# boost.net
KiCad netlist of a schematic drawn in Altium Designer
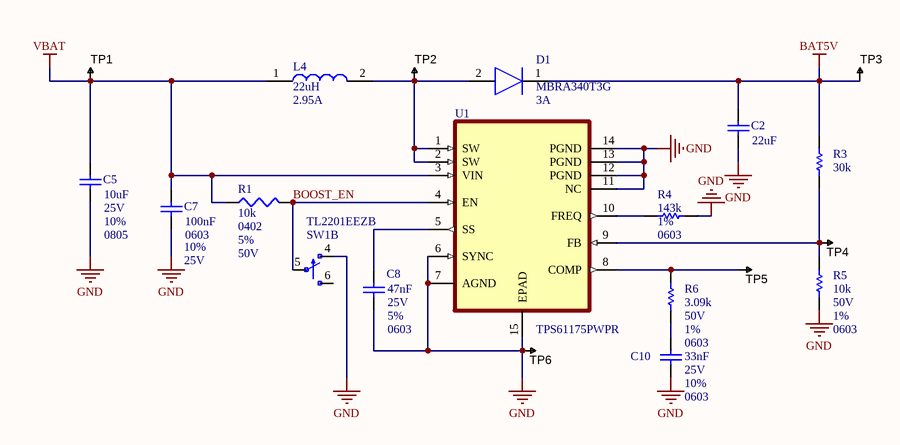
[diagram p0: boost.SchDoc]

(export (version "E")
  (design (tool "Eeschema 10.0.6"))
  (components
    (comp (ref "C2")
      (value "22uF")
      (footprint "C0805")
      (description "Capacitor")
      (fields (field (name "Comment") "Cap Semi"))
      (libsource (lib "SamacSys") (part "Cap Semi_1"))
    )
    (comp (ref "C5")
      (value "10uF")
      (footprint "C0805")
      (description "Capacitor")
      (fields
        (field (name "MANUFACTURER") "Murata")
        (field (name "MANUFACTURER PART NUMBER") "GRM21BR61E106KA73K")
        (field (name "CASE/PACKAGE") "0805")
        (field (name "TOLERANCE") "10%")
        (field (name "VOLTAGE RATING (DC)") "25V")
      )
      (libsource (lib "SamacSys") (part "Cap Semi_1"))
    )
    (comp (ref "C7")
      (value "100nF")
      (footprint "C0603")
      (description "Capacitor")
      (fields
        (field (name "MANUFACTURER") "Yageo")
        (field (name "MANUFACTURER PART NUMBER") "CC0603KRX7R8BB104")
        (field (name "CASE/PACKAGE") "0603")
        (field (name "TOLERANCE") "10%")
        (field (name "VOLTAGE") "25V")
      )
      (libsource (lib "SamacSys") (part "Cap Semi_1"))
    )
    (comp (ref "C8")
      (value "47nF")
      (footprint "C0603")
      (description "Capacitor")
      (fields
        (field (name "MANUFACTURER") "KEMET")
        (field (name "MANUFACTURER PART NUMBER") "C0603C473J3RACTU")
        (field (name "CASE/PACKAGE") "0603")
        (field (name "TOLERANCE") "5%")
        (field (name "VOLTAGE RATING") "25V")
      )
      (libsource (lib "SamacSys") (part "Cap Semi_1"))
    )
    (comp (ref "C10")
      (value "33nF")
      (footprint "C0603")
      (description "Capacitor")
      (fields
        (field (name "MANUFACTURER") "KEMET")
        (field (name "MANUFACTURER PART NUMBER") "C0603C333K3RACTU")
        (field (name "CASE/PACKAGE") "0603")
        (field (name "TOLERANCE") "10%")
        (field (name "VOLTAGE RATING (DC)") "25V")
      )
      (libsource (lib "SamacSys") (part "Cap Semi_1"))
    )
    (comp (ref "D1")
      (value "MBRA340T3G")
      (footprint "MBRA340T3G")
      (description "Diode")
      (fields
        (field (name "MOUSER PART NUMBER") "863-MBRA340T3G")
        (field (name "MANUFACTURER") "ON Semiconductor")
        (field (name "FORWARD CURRENT") "3A")
      )
      (libsource (lib "SamacSys") (part "MBRA340T3G"))
    )
    (comp (ref "L4")
      (value "22uH")
      (footprint "CDRH105RNP-220NC")
      (description "FIXED IND 22UH 2.9A 61 MOHM SMD")
      (fields
        (field (name "MANUFACTURER") "Sumida")
        (field (name "MANUFACTURER PART NUMBER") "CDRH105RNP-220NC")
        (field (name "SATURATION CURRENT") "2.95A")
      )
      (libsource (lib "SamacSys") (part "CDRH105RNP-220NC"))
    )
    (comp (ref "R1")
      (value "10k")
      (footprint "R0402")
      (description "Resistor")
      (fields
        (field (name "MANUFACTURER") "TE Connectivity")
        (field (name "MANUFACTURER PART NUMBER") "CRG0402J10K/10")
        (field (name "CASE/PACKAGE") "0402")
        (field (name "TOLERANCE") "5%")
        (field (name "VOLTAGE RATING") "50V")
      )
      (libsource (lib "Miscellaneous Devices") (part "Res3"))
    )
    (comp (ref "R3")
      (value "30k")
      (footprint "R0603")
      (description "Resistor")
      (fields (field (name "Comment") "Res3"))
      (libsource (lib "SamacSys") (part "Res1_2"))
    )
    (comp (ref "R4")
      (value "143k")
      (footprint "R0603")
      (description "Resistor")
      (fields
        (field (name "MANUFACTURER") "Stackpole Electronics")
        (field (name "MANUFACTURER PART NUMBER") "RMCF0603FT143K")
        (field (name "CASE/PACKAGE") "0603")
        (field (name "TOLERANCE") "1%")
      )
      (libsource (lib "SamacSys") (part "Res1_2"))
    )
    (comp (ref "R5")
      (value "10k")
      (footprint "R0603")
      (description "Resistor")
      (fields
        (field (name "MANUFACTURER") "TE Connectivity Neohm")
        (field (name "MANUFACTURER PART NUMBER") "CPF0603F10KC1")
        (field (name "CASE/PACKAGE") "0603")
        (field (name "TOLERANCE") "1%")
        (field (name "VOLTAGE RATING") "50V")
      )
      (libsource (lib "SamacSys") (part "Res1_2"))
    )
    (comp (ref "R6")
      (value "3.09k")
      (footprint "R0603")
      (description "Resistor")
      (fields
        (field (name "MANUFACTURER") "Yageo")
        (field (name "MANUFACTURER PART NUMBER") "RC0603FR-073K09L")
        (field (name "CASE/PACKAGE") "0603")
        (field (name "TOLERANCE") "1%")
        (field (name "VOLTAGE RATING (DC)") "50V")
      )
      (libsource (lib "SamacSys") (part "Res1_2"))
    )
    (comp (ref "SW1")
      (value "TL2201EEZB")
      (footprint "TL2201EEZB")
      (description "Pushbutton Switch DPDT Standard Through Hole")
      (fields (field (name "MF") "E-Switch"))
      (libsource (lib "Component_1") (part "TL2201EEZB"))
    )
    (comp (ref "TP1")
      (value "TESTPOINT")
      (footprint "TP-R60")
      (description "SMD test pin")
      (libsource (lib "PBL - Test Points") (part "TESTPOINT"))
    )
    (comp (ref "TP2")
      (value "TESTPOINT")
      (footprint "TP-R60")
      (description "SMD test pin")
      (libsource (lib "PBL - Test Points") (part "TESTPOINT"))
    )
    (comp (ref "TP3")
      (value "TESTPOINT")
      (footprint "TP-R60")
      (description "SMD test pin")
      (libsource (lib "PBL - Test Points") (part "TESTPOINT"))
    )
    (comp (ref "TP4")
      (value "TESTPOINT")
      (footprint "TP-R60")
      (description "SMD test pin")
      (libsource (lib "PBL - Test Points") (part "TESTPOINT"))
    )
    (comp (ref "TP5")
      (value "TESTPOINT")
      (footprint "TP-R60")
      (description "SMD test pin")
      (libsource (lib "PBL - Test Points") (part "TESTPOINT"))
    )
    (comp (ref "TP6")
      (value "TESTPOINT")
      (footprint "TP-R60")
      (description "SMD test pin")
      (libsource (lib "PBL - Test Points") (part "TESTPOINT"))
    )
    (comp (ref "U1")
      (value "TPS61175PWPR")
      (footprint "TPS61175PWPR")
      (description "IC REG MULTI CONFG ADJ 14HTSSOP")
      (fields (field (name "MANUFACTURER") "Texas Instruments"))
      (libsource (lib "SamacSys") (part "TPS61175PWPR"))
    )
  )
  (nets
    (net (code "1") (name "/BOOST_EN") (class "Default")
      (node (ref "R1") (pin "2") (pinfunction "2_2") (pintype "passive"))
      (node (ref "SW1") (pin "5") (pinfunction "P_5") (pintype "passive"))
      (node (ref "U1") (pin "4") (pinfunction "EN_4") (pintype "input"))
    )
    (net (code "2") (name "BAT5V") (class "Default")
      (node (ref "C2") (pin "2") (pinfunction "2_2") (pintype "passive"))
      (node (ref "D1") (pin "1") (pinfunction "K_1") (pintype "passive"))
      (node (ref "R3") (pin "1") (pinfunction "1_1") (pintype "passive"))
      (node (ref "TP3") (pin "1") (pintype "passive"))
    )
    (net (code "3") (name "GND") (class "Default")
      (node (ref "C10") (pin "1") (pinfunction "1_1") (pintype "passive"))
      (node (ref "C2") (pin "1") (pinfunction "1_1") (pintype "passive"))
      (node (ref "C5") (pin "1") (pinfunction "1_1") (pintype "passive"))
      (node (ref "C7") (pin "1") (pinfunction "1_1") (pintype "passive"))
      (node (ref "C8") (pin "1") (pinfunction "1_1") (pintype "passive"))
      (node (ref "R4") (pin "1") (pinfunction "1_1") (pintype "passive"))
      (node (ref "R5") (pin "2") (pinfunction "2_2") (pintype "passive"))
      (node (ref "SW1") (pin "4") (pinfunction "O_4") (pintype "passive"))
      (node (ref "TP6") (pin "1") (pintype "passive"))
      (node (ref "U1") (pin "11") (pinfunction "NC_11") (pintype "passive"))
      (node (ref "U1") (pin "12") (pinfunction "PGND_12") (pintype "power_in"))
      (node (ref "U1") (pin "13") (pinfunction "PGND_13") (pintype "power_in"))
      (node (ref "U1") (pin "14") (pinfunction "PGND_14") (pintype "power_in"))
      (node (ref "U1") (pin "15") (pinfunction "EPAD_15") (pintype "power_in"))
      (node (ref "U1") (pin "6") (pinfunction "SYNC_6") (pintype "input"))
      (node (ref "U1") (pin "7") (pinfunction "AGND_7") (pintype "power_in"))
    )
    (net (code "4") (name "Net-(C10-Pad2)") (class "Default")
      (node (ref "C10") (pin "2") (pinfunction "2_2") (pintype "passive"))
      (node (ref "R6") (pin "2") (pinfunction "2_2") (pintype "passive"))
    )
    (net (code "5") (name "Net-(D1-A)") (class "Default")
      (node (ref "D1") (pin "2") (pinfunction "A_2") (pintype "passive"))
      (node (ref "L4") (pin "2") (pinfunction "2_2") (pintype "passive"))
      (node (ref "TP2") (pin "1") (pintype "passive"))
      (node (ref "U1") (pin "1") (pinfunction "SW_1") (pintype "input"))
      (node (ref "U1") (pin "2") (pinfunction "SW_2") (pintype "input"))
    )
    (net (code "6") (name "Net-(U1-COMP)") (class "Default")
      (node (ref "R6") (pin "1") (pinfunction "1_1") (pintype "passive"))
      (node (ref "TP5") (pin "1") (pintype "passive"))
      (node (ref "U1") (pin "8") (pinfunction "COMP_8") (pintype "output"))
    )
    (net (code "7") (name "Net-(U1-FB)") (class "Default")
      (node (ref "R3") (pin "2") (pinfunction "2_2") (pintype "passive"))
      (node (ref "R5") (pin "1") (pinfunction "1_1") (pintype "passive"))
      (node (ref "TP4") (pin "1") (pintype "passive"))
      (node (ref "U1") (pin "9") (pinfunction "FB_9") (pintype "input"))
    )
    (net (code "8") (name "Net-(U1-FREQ)") (class "Default")
      (node (ref "R4") (pin "2") (pinfunction "2_2") (pintype "passive"))
      (node (ref "U1") (pin "10") (pinfunction "FREQ_10") (pintype "output"))
    )
    (net (code "9") (name "Net-(U1-SS)") (class "Default")
      (node (ref "C8") (pin "2") (pinfunction "2_2") (pintype "passive"))
      (node (ref "U1") (pin "5") (pinfunction "SS_5") (pintype "output"))
    )
    (net (code "10") (name "VBAT") (class "Default")
      (node (ref "C5") (pin "2") (pinfunction "2_2") (pintype "passive"))
      (node (ref "C7") (pin "2") (pinfunction "2_2") (pintype "passive"))
      (node (ref "L4") (pin "1") (pinfunction "1_1") (pintype "passive"))
      (node (ref "R1") (pin "1") (pinfunction "1_1") (pintype "passive"))
      (node (ref "TP1") (pin "1") (pintype "passive"))
      (node (ref "U1") (pin "3") (pinfunction "VIN_3") (pintype "input"))
    )
    (net (code "11") (name "unconnected-(SW1B-S-Pad6)") (class "Default")
      (node (ref "SW1") (pin "6") (pinfunction "S_6") (pintype "passive"))
    )
  )
)
